# littleWire-PTH_turned.net
KiCad netlist of a schematic drawn in EAGLE
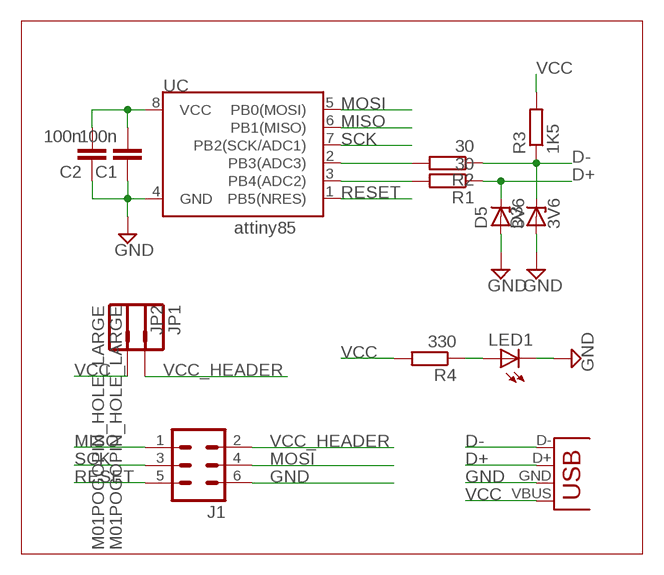
[diagram p0: schematic, sheet 1]

(export (version "E")
  (design (tool "Eeschema 10.0.6"))
  (components
    (comp (ref "C1")
      (value "100n")
      (footprint "eagle-import:C025-025X050")
      (libsource (lib "eagle-import") (part "C-EU025-025X050"))
    )
    (comp (ref "C2")
      (value "100n")
      (footprint "eagle-import:C025-025X050")
      (libsource (lib "eagle-import") (part "C-EU025-025X050"))
    )
    (comp (ref "D3")
      (value "3V6")
      (footprint "eagle-import:ZDIO-2.5")
      (libsource (lib "eagle-import") (part "ZENER-DIODEZD-2.5"))
    )
    (comp (ref "D5")
      (value "3V6")
      (footprint "eagle-import:ZDIO-7.5")
      (libsource (lib "eagle-import") (part "ZENER-DIODEZD-7.5"))
    )
    (comp (ref "J1")
      (value "ML6")
      (footprint "eagle-import:ML6")
      (libsource (lib "eagle-import") (part "ML6"))
    )
    (comp (ref "JP1")
      (value "M01POGOPIN_HOLE_LARGE")
      (footprint "eagle-import:1X01_POGOPIN_HOLE_LARGE")
      (libsource (lib "eagle-import") (part "M01POGOPIN_HOLE_LARGE"))
    )
    (comp (ref "JP2")
      (value "M01POGOPIN_HOLE_LARGE")
      (footprint "eagle-import:1X01_POGOPIN_HOLE_LARGE")
      (libsource (lib "eagle-import") (part "M01POGOPIN_HOLE_LARGE"))
    )
    (comp (ref "LED1")
      (value "LED3MM")
      (footprint "eagle-import:LED3MM")
      (libsource (lib "eagle-import") (part "LED3MM"))
    )
    (comp (ref "R1")
      (value "30")
      (footprint "eagle-import:0207_2V")
      (libsource (lib "eagle-import") (part "R-EU_0207/2V"))
    )
    (comp (ref "R2")
      (value "30")
      (footprint "eagle-import:0207_2V")
      (libsource (lib "eagle-import") (part "R-EU_0207/2V"))
    )
    (comp (ref "R3")
      (value "1K5")
      (footprint "eagle-import:0207_2V")
      (libsource (lib "eagle-import") (part "R-EU_0207/2V"))
    )
    (comp (ref "R4")
      (value "330")
      (footprint "eagle-import:0207_2V")
      (libsource (lib "eagle-import") (part "R-EU_0207/2V"))
    )
    (comp (ref "UC")
      (value "ATTINY45DIP8")
      (footprint "eagle-import:DIP08")
      (libsource (lib "eagle-import") (part "ATTINY45DIP8"))
    )
    (comp (ref "X1")
      (value "USB-A-H")
      (footprint "eagle-import:USB-A-H")
      (libsource (lib "eagle-import") (part "USB-A-H"))
    )
  )
  (nets
    (net (code "1") (name "/D+") (class "Default")
      (node (ref "D5") (pin "C") (pinfunction "C_C") (pintype "passive"))
      (node (ref "R1") (pin "1") (pinfunction "1_1") (pintype "passive"))
      (node (ref "X1") (pin "D+") (pinfunction "D-_D+") (pintype "bidirectional"))
    )
    (net (code "2") (name "/D-") (class "Default")
      (node (ref "D3") (pin "C") (pinfunction "C_C") (pintype "passive"))
      (node (ref "R2") (pin "1") (pinfunction "1_1") (pintype "passive"))
      (node (ref "R3") (pin "1") (pinfunction "1_1") (pintype "passive"))
      (node (ref "X1") (pin "D-") (pinfunction "D+_D-") (pintype "bidirectional"))
    )
    (net (code "3") (name "/MISO") (class "Default")
      (node (ref "J1") (pin "1") (pinfunction "1_1") (pintype "passive"))
      (node (ref "UC") (pin "6") (pinfunction "PB1(MISO)_6") (pintype "bidirectional"))
    )
    (net (code "4") (name "/MOSI") (class "Default")
      (node (ref "J1") (pin "4") (pinfunction "4_4") (pintype "passive"))
      (node (ref "UC") (pin "5") (pinfunction "PB0(MOSI)_5") (pintype "bidirectional"))
    )
    (net (code "5") (name "/RESET") (class "Default")
      (node (ref "J1") (pin "5") (pinfunction "5_5") (pintype "passive"))
      (node (ref "UC") (pin "1") (pinfunction "PB5(NRES)_1") (pintype "bidirectional"))
    )
    (net (code "6") (name "/SCK") (class "Default")
      (node (ref "J1") (pin "3") (pinfunction "3_3") (pintype "passive"))
      (node (ref "UC") (pin "7") (pinfunction "PB2(SCK/ADC1)_7") (pintype "bidirectional"))
    )
    (net (code "7") (name "/VCC") (class "Default")
      (node (ref "C1") (pin "2") (pinfunction "2_2") (pintype "passive"))
      (node (ref "C2") (pin "2") (pinfunction "2_2") (pintype "passive"))
      (node (ref "JP2") (pin "1") (pinfunction "1_1") (pintype "passive"))
      (node (ref "R3") (pin "2") (pinfunction "2_2") (pintype "passive"))
      (node (ref "R4") (pin "2") (pinfunction "2_2") (pintype "passive"))
      (node (ref "UC") (pin "8") (pinfunction "VCC_8") (pintype "bidirectional"))
      (node (ref "X1") (pin "VBUS") (pinfunction "GND_VBUS") (pintype "bidirectional"))
    )
    (net (code "8") (name "/VCC_HEADER") (class "Default")
      (node (ref "J1") (pin "2") (pinfunction "2_2") (pintype "passive"))
      (node (ref "JP1") (pin "1") (pinfunction "1_1") (pintype "passive"))
    )
    (net (code "9") (name "GND") (class "Default")
      (node (ref "C1") (pin "1") (pinfunction "1_1") (pintype "passive"))
      (node (ref "C2") (pin "1") (pinfunction "1_1") (pintype "passive"))
      (node (ref "D3") (pin "A") (pinfunction "A_A") (pintype "passive"))
      (node (ref "D5") (pin "A") (pinfunction "A_A") (pintype "passive"))
      (node (ref "J1") (pin "6") (pinfunction "6_6") (pintype "passive"))
      (node (ref "LED1") (pin "K") (pinfunction "C_K") (pintype "passive"))
      (node (ref "UC") (pin "4") (pinfunction "GND_4") (pintype "bidirectional"))
      (node (ref "X1") (pin "GND") (pinfunction "VBUS_GND") (pintype "bidirectional"))
    )
    (net (code "10") (name "Net-(LED1-PadA)") (class "Default")
      (node (ref "LED1") (pin "A") (pinfunction "A_A") (pintype "passive"))
      (node (ref "R4") (pin "1") (pinfunction "1_1") (pintype "passive"))
    )
    (net (code "11") (name "Net-(UC-PB3(ADC3))") (class "Default")
      (node (ref "R2") (pin "2") (pinfunction "2_2") (pintype "passive"))
      (node (ref "UC") (pin "2") (pinfunction "PB3(ADC3)_2") (pintype "bidirectional"))
    )
    (net (code "12") (name "Net-(UC-PB4(ADC2))") (class "Default")
      (node (ref "R1") (pin "2") (pinfunction "2_2") (pintype "passive"))
      (node (ref "UC") (pin "3") (pinfunction "PB4(ADC2)_3") (pintype "bidirectional"))
    )
  )
)
